# sixuanyi.net
KiCad netlist of a schematic drawn in Altium Designer
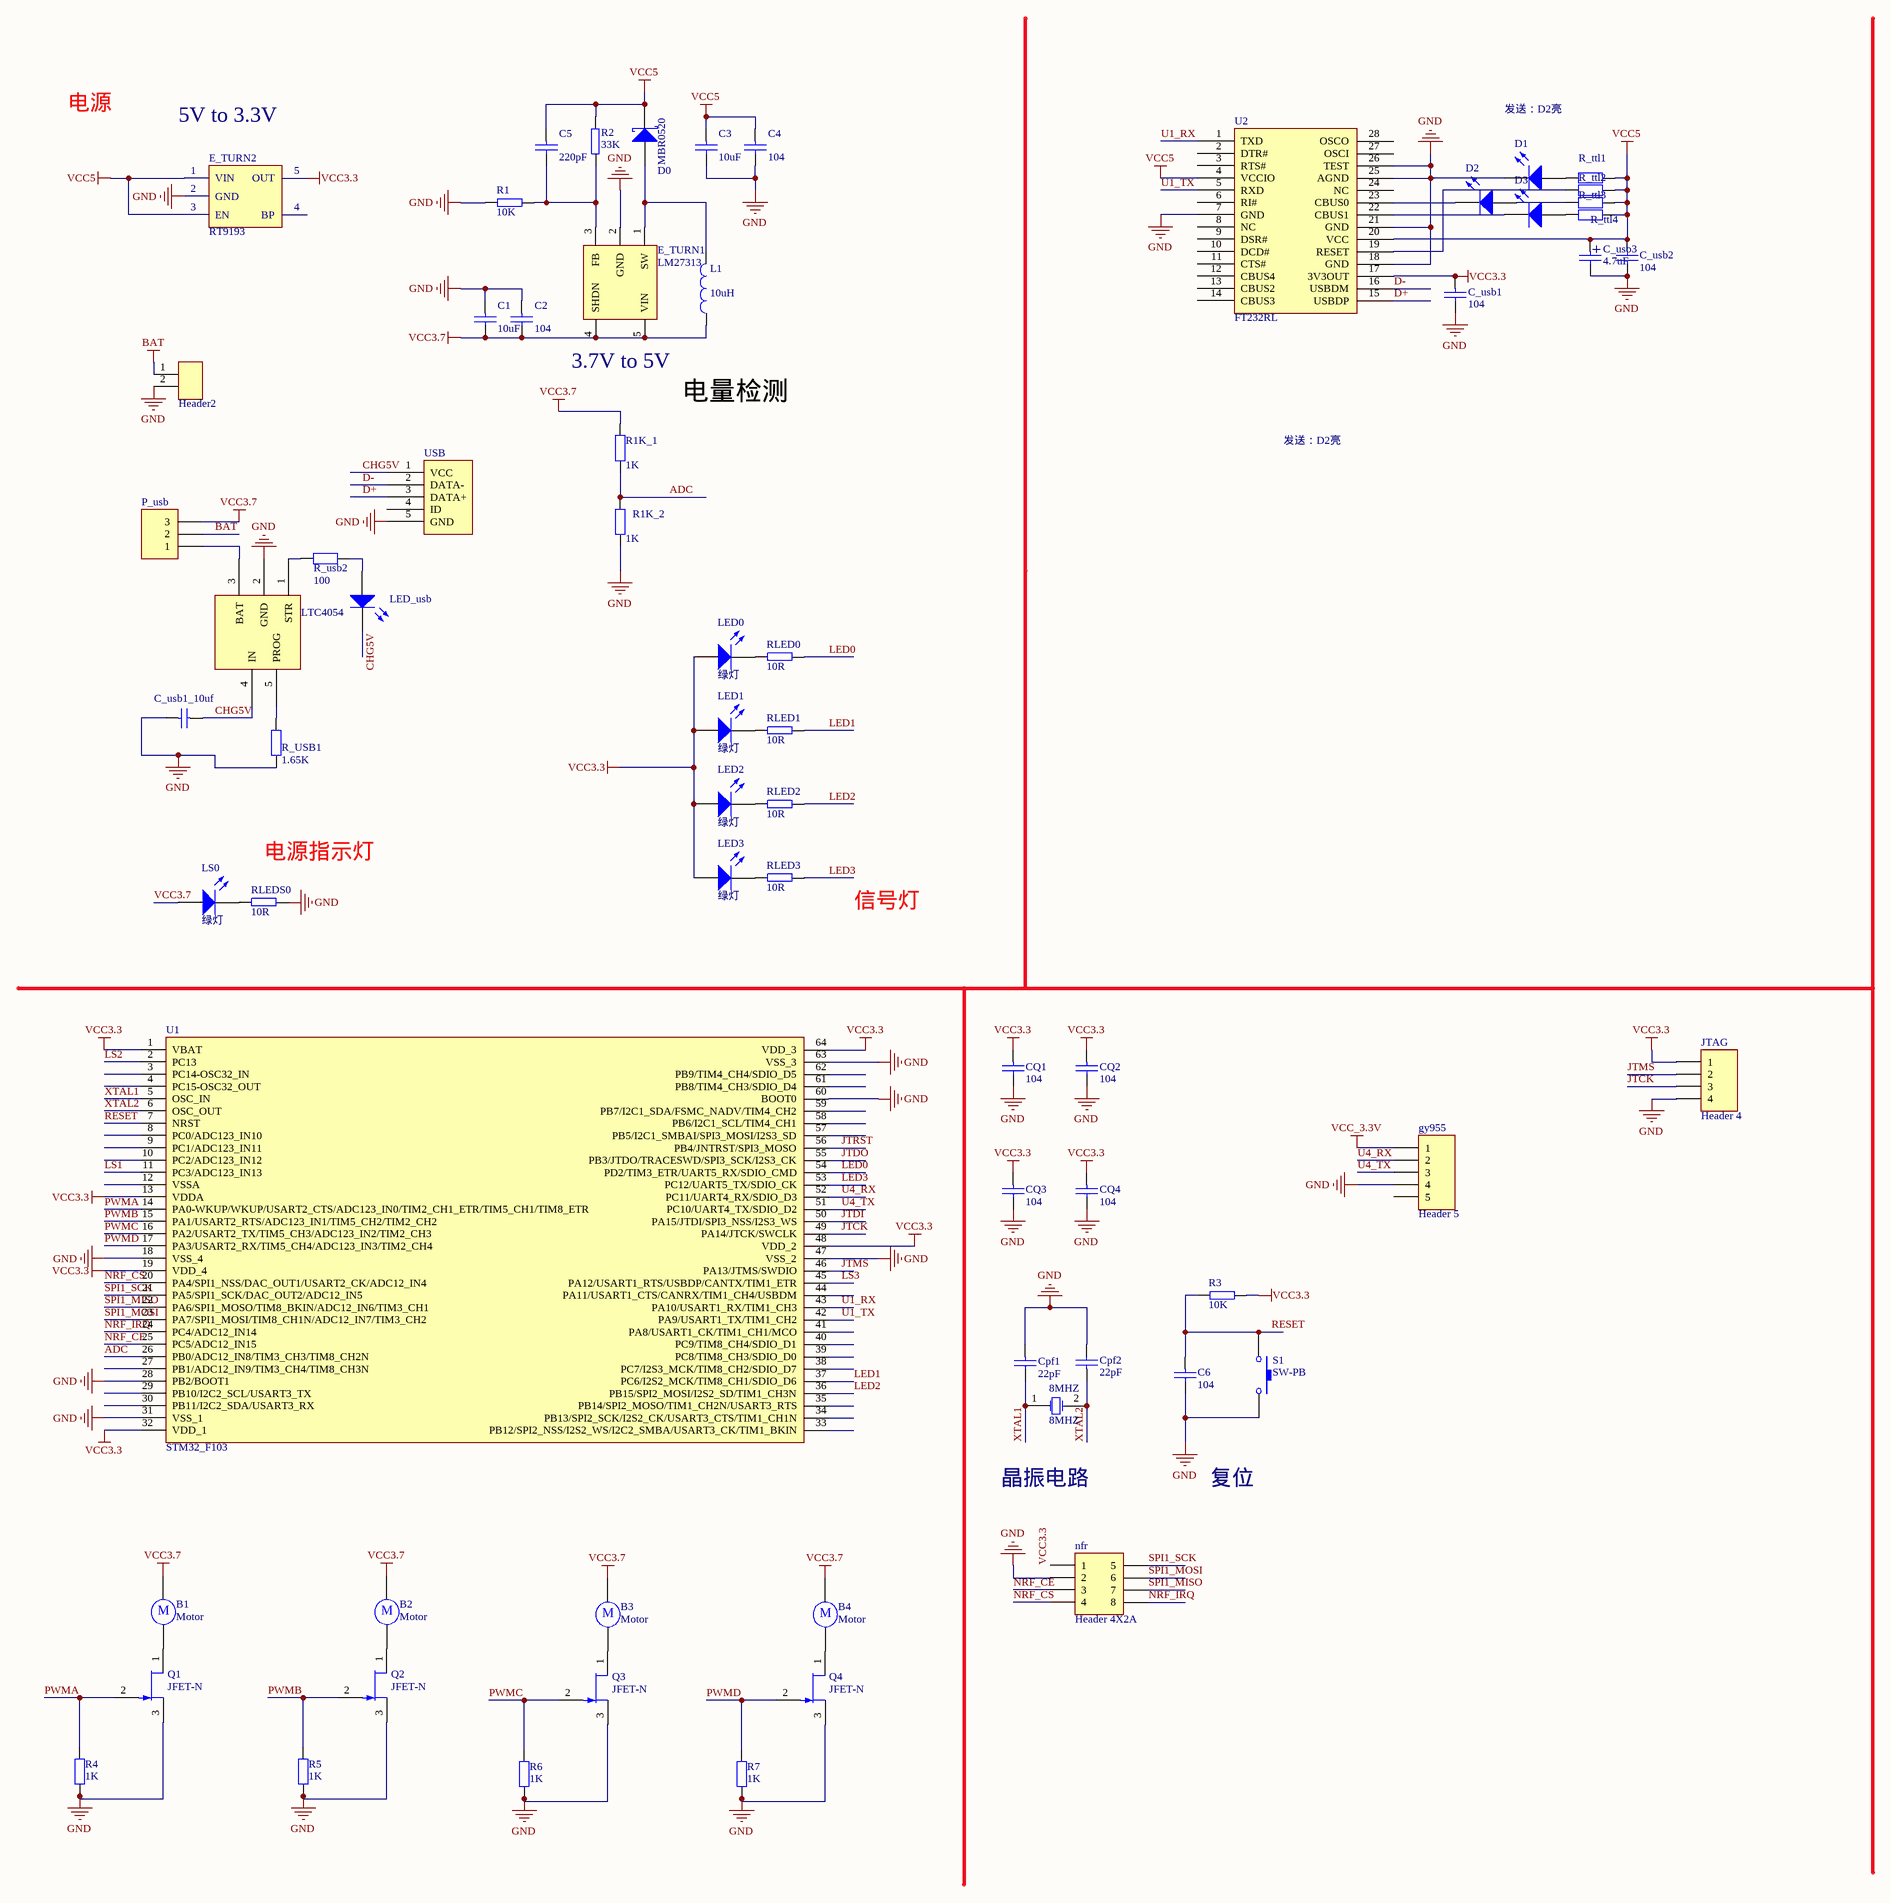
[diagram p0: sixuanyi.SchDoc]

(export (version "E")
  (design (tool "Eeschema 10.0.6"))
  (components
    (comp (ref "8MHZ")
      (value "8MHZ")
      (footprint "XTAL_D")
      (description "Crystal Oscillator")
      (fields (field (name "PUBLISHER") "Altium Limited"))
      (libsource (lib "TiCao") (part "XTAL"))
    )
    (comp (ref "B1")
      (value "Motor")
      (footprint "RB5-10.5")
      (description "Motor, General Kind")
      (fields (field (name "PUBLISHER") "Altium Limited"))
      (libsource (lib "Miscellaneous Devices") (part "Motor"))
    )
    (comp (ref "B2")
      (value "Motor")
      (footprint "RB5-10.5")
      (description "Motor, General Kind")
      (fields (field (name "PUBLISHER") "Altium Limited"))
      (libsource (lib "Miscellaneous Devices") (part "Motor"))
    )
    (comp (ref "B3")
      (value "Motor")
      (footprint "RB5-10.5")
      (description "Motor, General Kind")
      (fields (field (name "PUBLISHER") "Altium Limited"))
      (libsource (lib "Miscellaneous Devices") (part "Motor"))
    )
    (comp (ref "B4")
      (value "Motor")
      (footprint "RB5-10.5")
      (description "Motor, General Kind")
      (fields (field (name "PUBLISHER") "Altium Limited"))
      (libsource (lib "Miscellaneous Devices") (part "Motor"))
    )
    (comp (ref "C1") (value "10uF") (footprint "0603p") (libsource (lib "Sizhou") (part "CAP_WYN")))
    (comp (ref "C2") (value "104") (footprint "0603p") (libsource (lib "Sizhou") (part "CAP_WYN")))
    (comp (ref "C3") (value "10uF") (footprint "0603_WYN") (libsource (lib "Sizhou") (part "CAP_WYN")))
    (comp (ref "C4") (value "104") (footprint "0603_WYN") (libsource (lib "Sizhou") (part "CAP_WYN")))
    (comp (ref "C5") (value "220pF") (footprint "0603_WYN") (libsource (lib "Sizhou") (part "CAP_WYN")))
    (comp (ref "C6") (value "104") (footprint "0603_WYN") (libsource (lib "main") (part "CAP_WYN")))
    (comp (ref "Cpf1") (value "22pF") (footprint "0603_WYN") (libsource (lib "main") (part "CAP_WYN")))
    (comp (ref "Cpf2") (value "22pF") (footprint "0603_WYN") (libsource (lib "main") (part "CAP_WYN")))
    (comp (ref "CQ1") (value "104") (footprint "0603_WYN") (libsource (lib "main") (part "CAP_WYN")))
    (comp (ref "CQ2") (value "104") (footprint "0603_WYN") (libsource (lib "main") (part "CAP_WYN")))
    (comp (ref "CQ3") (value "104") (footprint "0603_WYN") (libsource (lib "main") (part "CAP_WYN")))
    (comp (ref "CQ4") (value "104") (footprint "0603_WYN") (libsource (lib "main") (part "CAP_WYN")))
    (comp (ref "C_usb1") (value "104") (footprint "0603P") (libsource (lib "main") (part "CAP_WYN")))
    (comp (ref "C_usb1_10uf")
      (value "C_usb1_10uf")
      (footprint "0603p")
      (description "Capacitor")
      (fields (field (name "PUBLISHER") "Altium Limited"))
      (libsource (lib "Miscellaneous Devices") (part "Cap"))
    )
    (comp (ref "C_usb2") (value "104") (footprint "0603P") (libsource (lib "main") (part "CAP_WYN")))
    (comp (ref "C_usb3")
      (value "4.7uF")
      (footprint "1206")
      (libsource (lib "PCB_PROJECT1") (part "CAP_POL_WYN"))
    )
    (comp (ref "D0")
      (value "MBR0520")
      (footprint "SMB")
      (description "Schottky Diode")
      (fields (field (name "PUBLISHER") "Altium Limited"))
      (libsource (lib "Miscellaneous Devices") (part "D Schottky"))
    )
    (comp (ref "D1")
      (value "LED2")
      (footprint "SMDLED")
      (description "Typical RED, GREEN, YELLOW, AMBER GaAs LED")
      (fields (field (name "PUBLISHER") "Altium Limited"))
      (libsource (lib "Miscellaneous Devices") (part "LED2"))
    )
    (comp (ref "D2")
      (value "LED2")
      (footprint "SMDLED")
      (description "Typical RED, GREEN, YELLOW, AMBER GaAs LED")
      (fields (field (name "PUBLISHER") "Altium Limited"))
      (libsource (lib "Miscellaneous Devices") (part "LED2"))
    )
    (comp (ref "D3")
      (value "LED2")
      (footprint "SMDLED")
      (description "Typical RED, GREEN, YELLOW, AMBER GaAs LED")
      (fields (field (name "PUBLISHER") "Altium Limited"))
      (libsource (lib "Miscellaneous Devices") (part "LED2"))
    )
    (comp (ref "E_TURN1") (value "LM27313") (footprint "SOT23-6") (libsource (lib "Sizhou") (part "LM27313")))
    (comp (ref "E_TURN2") (value "RT9193") (footprint "SOT23-6") (libsource (lib "Sizhou") (part "RT9193")))
    (comp (ref "gy955")
      (value "Header 5")
      (footprint "HDR1X5")
      (description "Header, 5-Pin")
      (fields (field (name "PUBLISHER") "Altium Limited"))
      (libsource (lib "Miscellaneous Connectors") (part "Header 5"))
    )
    (comp (ref "JTAG")
      (value "Header 4")
      (footprint "HDR1X4")
      (description "Header, 4-Pin")
      (fields (field (name "PUBLISHER") "Altium Limited"))
      (libsource (lib "Miscellaneous Connectors") (part "Header 4"))
    )
    (comp (ref "L1")
      (value "10uH")
      (footprint "0805_WYN")
      (description "Inductor")
      (fields (field (name "PUBLISHER") "Altium Limited"))
      (libsource (lib "Miscellaneous Devices") (part "Inductor"))
    )
    (comp (ref "LED0")
      (value "绿灯")
      (footprint "0603_WYN")
      (description "Typical RED, GREEN, YELLOW, AMBER GaAs LED")
      (fields (field (name "PUBLISHER") "Altium Limited"))
      (libsource (lib "main") (part "LED_WYN"))
    )
    (comp (ref "LED1")
      (value "绿灯")
      (footprint "0603_WYN")
      (description "Typical RED, GREEN, YELLOW, AMBER GaAs LED")
      (fields (field (name "PUBLISHER") "Altium Limited"))
      (libsource (lib "main") (part "LED_WYN"))
    )
    (comp (ref "LED2")
      (value "绿灯")
      (footprint "0603_WYN")
      (description "Typical RED, GREEN, YELLOW, AMBER GaAs LED")
      (fields (field (name "PUBLISHER") "Altium Limited"))
      (libsource (lib "main") (part "LED_WYN"))
    )
    (comp (ref "LED3")
      (value "绿灯")
      (footprint "0603_WYN")
      (description "Typical RED, GREEN, YELLOW, AMBER GaAs LED")
      (fields (field (name "PUBLISHER") "Altium Limited"))
      (libsource (lib "main") (part "LED_WYN"))
    )
    (comp (ref "LED_usb")
      (value "黄灯")
      (footprint "极性0805_WYN")
      (description "Typical RED GaAs LED")
      (fields (field (name "PUBLISHER") "Altium Limited"))
      (libsource (lib "救援1") (part "LED1"))
    )
    (comp (ref "LS0")
      (value "绿灯")
      (footprint "0603_WYN")
      (description "Typical RED, GREEN, YELLOW, AMBER GaAs LED")
      (fields (field (name "PUBLISHER") "Altium Limited"))
      (libsource (lib "main") (part "LED_WYN"))
    )
    (comp (ref "LTC4054") (value "LTC4054") (footprint "SOT23-6") (libsource (lib "救援2") (part "LTC4054")))
    (comp (ref "nfr")
      (value "Header 4X2A")
      (footprint "24L01-L")
      (description "Header, 4-Pin, Dual row")
      (fields (field (name "PUBLISHER") "Altium Limited"))
      (libsource (lib "Miscellaneous Connectors") (part "Header 4X2A"))
    )
    (comp (ref "power") (value "Header2") (footprint "HDR1X2") (libsource (lib "救援2") (part "Header2")))
    (comp (ref "P_usb")
      (value "P_usb")
      (footprint "HDR1X3")
      (description "Header, 3-Pin")
      (fields (field (name "PUBLISHER") "Altium Limited"))
      (libsource (lib "Miscellaneous Connectors") (part "Header 3"))
    )
    (comp (ref "Q1")
      (value "JFET-N")
      (footprint "SI2302")
      (description "N-Channel JFET")
      (fields (field (name "PUBLISHER") "Altium Limited"))
      (libsource (lib "Miscellaneous Devices") (part "JFET-N"))
    )
    (comp (ref "Q2")
      (value "JFET-N")
      (footprint "SI2302")
      (description "N-Channel JFET")
      (fields (field (name "PUBLISHER") "Altium Limited"))
      (libsource (lib "Miscellaneous Devices") (part "JFET-N"))
    )
    (comp (ref "Q3")
      (value "JFET-N")
      (footprint "SI2302")
      (description "N-Channel JFET")
      (fields (field (name "PUBLISHER") "Altium Limited"))
      (libsource (lib "Miscellaneous Devices") (part "JFET-N"))
    )
    (comp (ref "Q4")
      (value "JFET-N")
      (footprint "SI2302")
      (description "N-Channel JFET")
      (fields (field (name "PUBLISHER") "Altium Limited"))
      (libsource (lib "Miscellaneous Devices") (part "JFET-N"))
    )
    (comp (ref "R1") (value "10K") (footprint "0603_WYN") (libsource (lib "main") (part "RES_WYN")))
    (comp (ref "R1K_1")
      (value "1K")
      (footprint "AXIAL-0.4")
      (description "Resistor")
      (fields (field (name "Comment") "Res2") (field (name "PUBLISHER") "Altium Limited"))
      (libsource (lib "Miscellaneous Devices") (part "Res2"))
    )
    (comp (ref "R1K_2")
      (value "1K")
      (footprint "AXIAL-0.4")
      (description "Resistor")
      (fields (field (name "Comment") "Res2") (field (name "PUBLISHER") "Altium Limited"))
      (libsource (lib "Miscellaneous Devices") (part "Res2"))
    )
    (comp (ref "R2") (value "33K") (footprint "0603_WYN") (libsource (lib "main") (part "RES_WYN")))
    (comp (ref "R3") (value "10K") (footprint "0603_WYN") (libsource (lib "main") (part "RES_WYN")))
    (comp (ref "R4")
      (value "1K")
      (footprint "AXIAL-0.4")
      (description "Resistor")
      (fields (field (name "Comment") "Res2") (field (name "PUBLISHER") "Altium Limited"))
      (libsource (lib "Miscellaneous Devices") (part "Res2"))
    )
    (comp (ref "R5")
      (value "1K")
      (footprint "AXIAL-0.4")
      (description "Resistor")
      (fields (field (name "Comment") "Res2") (field (name "PUBLISHER") "Altium Limited"))
      (libsource (lib "Miscellaneous Devices") (part "Res2"))
    )
    (comp (ref "R6")
      (value "1K")
      (footprint "AXIAL-0.4")
      (description "Resistor")
      (fields (field (name "Comment") "Res2") (field (name "PUBLISHER") "Altium Limited"))
      (libsource (lib "Miscellaneous Devices") (part "Res2"))
    )
    (comp (ref "R7")
      (value "1K")
      (footprint "AXIAL-0.4")
      (description "Resistor")
      (fields (field (name "Comment") "Res2") (field (name "PUBLISHER") "Altium Limited"))
      (libsource (lib "Miscellaneous Devices") (part "Res2"))
    )
    (comp (ref "RLED0") (value "10R") (footprint "0603_WYN") (libsource (lib "main") (part "RES_WYN")))
    (comp (ref "RLED1") (value "10R") (footprint "0603_WYN") (libsource (lib "main") (part "RES_WYN")))
    (comp (ref "RLED2") (value "10R") (footprint "0603_WYN") (libsource (lib "main") (part "RES_WYN")))
    (comp (ref "RLED3") (value "10R") (footprint "0603_WYN") (libsource (lib "main") (part "RES_WYN")))
    (comp (ref "RLEDS0") (value "10R") (footprint "0603_WYN") (libsource (lib "main") (part "RES_WYN")))
    (comp (ref "R_ttl1")
      (value "1K")
      (footprint "0603p")
      (description "Resistor")
      (fields (field (name "PUBLISHER") "Altium Limited"))
      (libsource (lib "救援1") (part "Res2"))
    )
    (comp (ref "R_ttl2")
      (value "1K")
      (footprint "0603p")
      (description "Resistor")
      (fields (field (name "PUBLISHER") "Altium Limited"))
      (libsource (lib "救援1") (part "Res2"))
    )
    (comp (ref "R_ttl3")
      (value "1K")
      (footprint "0603p")
      (description "Resistor")
      (fields (field (name "PUBLISHER") "Altium Limited"))
      (libsource (lib "救援1") (part "Res2"))
    )
    (comp (ref "R_ttl4")
      (value "1K")
      (footprint "0603p")
      (description "Resistor")
      (fields (field (name "PUBLISHER") "Altium Limited"))
      (libsource (lib "救援1") (part "Res2"))
    )
    (comp (ref "R_USB1")
      (value "R_USB1")
      (footprint "0603p")
      (description "Resistor")
      (fields (field (name "ALTIUM_VALUE") "1.65K") (field (name "PUBLISHER") "Altium Limited"))
      (libsource (lib "Miscellaneous Devices") (part "Res2"))
    )
    (comp (ref "R_usb2")
      (value "R_usb2")
      (footprint "0603p")
      (description "Resistor")
      (fields (field (name "ALTIUM_VALUE") "100") (field (name "PUBLISHER") "Altium Limited"))
      (libsource (lib "") (part "Res2_1"))
    )
    (comp (ref "S1")
      (value "SW-PB")
      (footprint "CLICK")
      (description "Switch")
      (fields (field (name "PUBLISHER") "Altium Limited"))
      (libsource (lib "Miscellaneous Devices") (part "SW-PB"))
    )
    (comp (ref "U1") (value "STM32_F103") (footprint "LQFP64") (libsource (lib "tes1") (part "STM32_F103")))
    (comp (ref "U2") (value "FT232RL") (footprint "SSOP-28") (libsource (lib "my_library") (part "FT232RL")))
    (comp (ref "USB")
      (value "usb mini")
      (footprint "USB - duplicate1")
      (libsource (lib "救援2") (part "usb mini"))
    )
  )
  (nets
    (net (code "1") (name "/ADC") (class "Default")
      (node (ref "R1K_1") (pin "1") (pinfunction "1_1") (pintype "passive"))
      (node (ref "R1K_2") (pin "2") (pinfunction "2_2") (pintype "passive"))
      (node (ref "U1") (pin "26") (pinfunction "PB0/ADC12_IN8/TIM3_CH3/TIM8_CH2N_26") (pintype "passive"))
    )
    (net (code "2") (name "/CHG5V") (class "Default")
      (node (ref "C_usb1_10uf") (pin "1") (pinfunction "1_1") (pintype "passive"))
      (node (ref "LED_usb") (pin "2") (pinfunction "K_2") (pintype "passive"))
      (node (ref "LTC4054") (pin "4") (pinfunction "IN_4") (pintype "passive"))
      (node (ref "USB") (pin "1") (pinfunction "VCC_1") (pintype "passive"))
    )
    (net (code "3") (name "/D+") (class "Default")
      (node (ref "U2") (pin "15") (pinfunction "USBDP_15") (pintype "passive"))
      (node (ref "USB") (pin "3") (pinfunction "DATA+_3") (pintype "passive"))
    )
    (net (code "4") (name "/D-") (class "Default")
      (node (ref "U2") (pin "16") (pinfunction "USBDM_16") (pintype "passive"))
      (node (ref "USB") (pin "2") (pinfunction "DATA-_2") (pintype "passive"))
    )
    (net (code "5") (name "/JTCK") (class "Default")
      (node (ref "JTAG") (pin "3") (pinfunction "3_3") (pintype "passive"))
      (node (ref "U1") (pin "49") (pinfunction "PA14/JTCK/SWCLK_49") (pintype "passive"))
    )
    (net (code "6") (name "/JTDI") (class "Default")
      (node (ref "U1") (pin "50") (pinfunction "PA15/JTDI/SPI3_NSS/I2S3_WS_50") (pintype "passive"))
    )
    (net (code "7") (name "/JTDO") (class "Default")
      (node (ref "U1") (pin "55") (pinfunction "PB3/JTDO/TRACESWD/SPI3_SCK/I2S3_CK_55") (pintype "passive"))
    )
    (net (code "8") (name "/JTMS") (class "Default")
      (node (ref "JTAG") (pin "2") (pinfunction "2_2") (pintype "passive"))
      (node (ref "U1") (pin "46") (pinfunction "PA13/JTMS/SWDIO_46") (pintype "passive"))
    )
    (net (code "9") (name "/JTRST") (class "Default")
      (node (ref "U1") (pin "56") (pinfunction "PB4/JNTRST/SPI3_MOSO_56") (pintype "passive"))
    )
    (net (code "10") (name "/LED0") (class "Default")
      (node (ref "RLED0") (pin "1") (pinfunction "1_1") (pintype "passive"))
      (node (ref "U1") (pin "54") (pinfunction "PD2/TIM3_ETR/UART5_RX/SDIO_CMD_54") (pintype "passive"))
    )
    (net (code "11") (name "/LED1") (class "Default")
      (node (ref "RLED1") (pin "1") (pinfunction "1_1") (pintype "passive"))
      (node (ref "U1") (pin "37") (pinfunction "PC6/I2S2_MCK/TIM8_CH1/SDIO_D6_37") (pintype "passive"))
    )
    (net (code "12") (name "/LED2") (class "Default")
      (node (ref "RLED2") (pin "1") (pinfunction "1_1") (pintype "passive"))
      (node (ref "U1") (pin "36") (pinfunction "PB15/SPI2_MOSI/I2S2_SD/TIM1_CH3N_36") (pintype "passive"))
    )
    (net (code "13") (name "/LED3") (class "Default")
      (node (ref "RLED3") (pin "1") (pinfunction "1_1") (pintype "passive"))
      (node (ref "U1") (pin "53") (pinfunction "PC12/UART5_TX/SDIO_CK_53") (pintype "passive"))
    )
    (net (code "14") (name "/LS1") (class "Default")
      (node (ref "U1") (pin "11") (pinfunction "PC3/ADC123_IN13_11") (pintype "passive"))
    )
    (net (code "15") (name "/LS2") (class "Default")
      (node (ref "U1") (pin "2") (pinfunction "PC13_2") (pintype "passive"))
    )
    (net (code "16") (name "/LS3") (class "Default")
      (node (ref "U1") (pin "45") (pinfunction "PA12/USART1_RTS/USBDP/CANTX/TIM1_ETR_45") (pintype "passive"))
    )
    (net (code "17") (name "/NRF_CE") (class "Default")
      (node (ref "U1") (pin "25") (pinfunction "PC5/ADC12_IN15_25") (pintype "passive"))
      (node (ref "nfr") (pin "3") (pinfunction "3_3") (pintype "passive"))
    )
    (net (code "18") (name "/NRF_CS") (class "Default")
      (node (ref "U1") (pin "20") (pinfunction "PA4/SPI1_NSS/DAC_OUT1/USART2_CK/ADC12_IN4_20") (pintype "passive"))
      (node (ref "nfr") (pin "4") (pinfunction "4_4") (pintype "passive"))
    )
    (net (code "19") (name "/NRF_IRQ") (class "Default")
      (node (ref "U1") (pin "24") (pinfunction "PC4/ADC12_IN14_24") (pintype "passive"))
      (node (ref "nfr") (pin "8") (pinfunction "8_8") (pintype "passive"))
    )
    (net (code "20") (name "/PWMA") (class "Default")
      (node (ref "Q1") (pin "2") (pinfunction "G_2") (pintype "passive"))
      (node (ref "R4") (pin "2") (pinfunction "2_2") (pintype "passive"))
      (node (ref "U1") (pin "14") (pinfunction "PA0-WKUP/WKUP/USART2_CTS/ADC123_IN0/TIM2_CH1_ETR/TIM5_CH1/TIM8_ETR_14") (pintype "passive"))
    )
    (net (code "21") (name "/PWMB") (class "Default")
      (node (ref "Q2") (pin "2") (pinfunction "G_2") (pintype "passive"))
      (node (ref "R5") (pin "2") (pinfunction "2_2") (pintype "passive"))
      (node (ref "U1") (pin "15") (pinfunction "PA1/USART2_RTS/ADC123_IN1/TIM5_CH2/TIM2_CH2_15") (pintype "passive"))
    )
    (net (code "22") (name "/PWMC") (class "Default")
      (node (ref "Q3") (pin "2") (pinfunction "G_2") (pintype "passive"))
      (node (ref "R6") (pin "2") (pinfunction "2_2") (pintype "passive"))
      (node (ref "U1") (pin "16") (pinfunction "PA2/USART2_TX/TIM5_CH3/ADC123_IN2/TIM2_CH3_16") (pintype "passive"))
    )
    (net (code "23") (name "/PWMD") (class "Default")
      (node (ref "Q4") (pin "2") (pinfunction "G_2") (pintype "passive"))
      (node (ref "R7") (pin "2") (pinfunction "2_2") (pintype "passive"))
      (node (ref "U1") (pin "17") (pinfunction "PA3/USART2_RX/TIM5_CH4/ADC123_IN3/TIM2_CH4_17") (pintype "passive"))
    )
    (net (code "24") (name "/RESET") (class "Default")
      (node (ref "C6") (pin "1") (pintype "passive"))
      (node (ref "R3") (pin "1") (pinfunction "1_1") (pintype "passive"))
      (node (ref "S1") (pin "1") (pinfunction "1_1") (pintype "passive"))
      (node (ref "U1") (pin "7") (pinfunction "NRST_7") (pintype "passive"))
    )
    (net (code "25") (name "/SPI1_MISO") (class "Default")
      (node (ref "U1") (pin "22") (pinfunction "PA6/SPI1_MOSO/TIM8_BKIN/ADC12_IN6/TIM3_CH1_22") (pintype "passive"))
      (node (ref "nfr") (pin "7") (pinfunction "7_7") (pintype "passive"))
    )
    (net (code "26") (name "/SPI1_MOSI") (class "Default")
      (node (ref "U1") (pin "23") (pinfunction "PA7/SPI1_MOSI/TIM8_CH1N/ADC12_IN7/TIM3_CH2_23") (pintype "passive"))
      (node (ref "nfr") (pin "6") (pinfunction "6_6") (pintype "passive"))
    )
    (net (code "27") (name "/SPI1_SCK") (class "Default")
      (node (ref "U1") (pin "21") (pinfunction "PA5/SPI1_SCK/DAC_OUT2/ADC12_IN5_21") (pintype "passive"))
      (node (ref "nfr") (pin "5") (pinfunction "5_5") (pintype "passive"))
    )
    (net (code "28") (name "/U1_RX") (class "Default")
      (node (ref "U1") (pin "43") (pinfunction "PA10/USART1_RX/TIM1_CH3_43") (pintype "passive"))
      (node (ref "U2") (pin "1") (pinfunction "TXD_1") (pintype "passive"))
    )
    (net (code "29") (name "/U1_TX") (class "Default")
      (node (ref "U1") (pin "42") (pinfunction "PA9/USART1_TX/TIM1_CH2_42") (pintype "passive"))
      (node (ref "U2") (pin "5") (pinfunction "RXD_5") (pintype "passive"))
    )
    (net (code "30") (name "/U4_RX") (class "Default")
      (node (ref "U1") (pin "52") (pinfunction "PC11/UART4_RX/SDIO_D3_52") (pintype "passive"))
      (node (ref "gy955") (pin "2") (pinfunction "2_2") (pintype "passive"))
    )
    (net (code "31") (name "/U4_TX") (class "Default")
      (node (ref "U1") (pin "51") (pinfunction "PC10/UART4_TX/SDIO_D2_51") (pintype "passive"))
      (node (ref "gy955") (pin "3") (pinfunction "3_3") (pintype "passive"))
    )
    (net (code "32") (name "/XTAL1") (class "Default")
      (node (ref "8MHZ") (pin "1") (pinfunction "OSC1_1") (pintype "passive"))
      (node (ref "Cpf1") (pin "2") (pintype "passive"))
      (node (ref "U1") (pin "5") (pinfunction "OSC_IN_5") (pintype "passive"))
    )
    (net (code "33") (name "/XTAL2") (class "Default")
      (node (ref "8MHZ") (pin "2") (pinfunction "OSC2_2") (pintype "passive"))
      (node (ref "Cpf2") (pin "1") (pintype "passive"))
      (node (ref "U1") (pin "6") (pinfunction "OSC_OUT_6") (pintype "passive"))
    )
    (net (code "34") (name "BAT") (class "Default")
      (node (ref "P_usb") (pin "2") (pinfunction "2_2") (pintype "passive"))
      (node (ref "power") (pin "1") (pintype "passive"))
    )
    (net (code "35") (name "GND") (class "Default")
      (node (ref "C1") (pin "1") (pintype "passive"))
      (node (ref "C2") (pin "1") (pintype "passive"))
      (node (ref "C3") (pin "2") (pintype "passive"))
      (node (ref "C4") (pin "2") (pintype "passive"))
      (node (ref "C6") (pin "2") (pintype "passive"))
      (node (ref "CQ1") (pin "2") (pintype "passive"))
      (node (ref "CQ2") (pin "2") (pintype "passive"))
      (node (ref "CQ3") (pin "2") (pintype "passive"))
      (node (ref "CQ4") (pin "2") (pintype "passive"))
      (node (ref "C_usb1") (pin "2") (pintype "passive"))
      (node (ref "C_usb1_10uf") (pin "2") (pinfunction "2_2") (pintype "passive"))
      (node (ref "C_usb2") (pin "2") (pintype "passive"))
      (node (ref "C_usb3") (pin "2") (pintype "passive"))
      (node (ref "Cpf1") (pin "1") (pintype "passive"))
      (node (ref "Cpf2") (pin "2") (pintype "passive"))
      (node (ref "D1") (pin "2") (pinfunction "K_2") (pintype "passive"))
      (node (ref "E_TURN1") (pin "2") (pinfunction "GND_2") (pintype "passive"))
      (node (ref "E_TURN2") (pin "2") (pinfunction "GND_2") (pintype "passive"))
      (node (ref "JTAG") (pin "4") (pinfunction "4_4") (pintype "passive"))
      (node (ref "LTC4054") (pin "2") (pinfunction "GND_2") (pintype "passive"))
      (node (ref "Q1") (pin "3") (pinfunction "S_3") (pintype "passive"))
      (node (ref "Q2") (pin "3") (pinfunction "S_3") (pintype "passive"))
      (node (ref "Q3") (pin "3") (pinfunction "S_3") (pintype "passive"))
      (node (ref "Q4") (pin "3") (pinfunction "S_3") (pintype "passive"))
      (node (ref "R1") (pin "1") (pinfunction "1_1") (pintype "passive"))
      (node (ref "R1K_2") (pin "1") (pinfunction "1_1") (pintype "passive"))
      (node (ref "R4") (pin "1") (pinfunction "1_1") (pintype "passive"))
      (node (ref "R5") (pin "1") (pinfunction "1_1") (pintype "passive"))
      (node (ref "R6") (pin "1") (pinfunction "1_1") (pintype "passive"))
      (node (ref "R7") (pin "1") (pinfunction "1_1") (pintype "passive"))
      (node (ref "RLEDS0") (pin "1") (pinfunction "1_1") (pintype "passive"))
      (node (ref "R_USB1") (pin "1") (pinfunction "1_1") (pintype "passive"))
      (node (ref "S1") (pin "2") (pinfunction "2_2") (pintype "passive"))
      (node (ref "U1") (pin "18") (pinfunction "VSS_4_18") (pintype "passive"))
      (node (ref "U1") (pin "28") (pinfunction "PB2/BOOT1_28") (pintype "passive"))
      (node (ref "U1") (pin "31") (pinfunction "VSS_1_31") (pintype "passive"))
      (node (ref "U1") (pin "47") (pinfunction "VSS_2_47") (pintype "passive"))
      (node (ref "U1") (pin "60") (pinfunction "BOOT0_60") (pintype "passive"))
      (node (ref "U1") (pin "63") (pinfunction "VSS_3_63") (pintype "passive"))
      (node (ref "U2") (pin "18") (pinfunction "GND_18") (pintype "passive"))
      (node (ref "U2") (pin "21") (pinfunction "GND_21") (pintype "passive"))
      (node (ref "U2") (pin "25") (pinfunction "AGND_25") (pintype "passive"))
      (node (ref "U2") (pin "26") (pinfunction "TEST_26") (pintype "passive"))
      (node (ref "U2") (pin "7") (pinfunction "GND_7") (pintype "passive"))
      (node (ref "USB") (pin "5") (pinfunction "GND_5") (pintype "passive"))
      (node (ref "gy955") (pin "4") (pinfunction "4_4") (pintype "passive"))
      (node (ref "nfr") (pin "2") (pinfunction "2_2") (pintype "passive"))
      (node (ref "power") (pin "2") (pintype "passive"))
    )
    (net (code "36") (name "Net-(D0-A)") (class "Default")
      (node (ref "D0") (pin "1") (pinfunction "A_1") (pintype "passive"))
      (node (ref "E_TURN1") (pin "1") (pinfunction "SW_1") (pintype "passive"))
      (node (ref "L1") (pin "2") (pinfunction "2_2") (pintype "passive"))
    )
    (net (code "37") (name "Net-(D1-A)") (class "Default")
      (node (ref "D1") (pin "1") (pinfunction "A_1") (pintype "passive"))
      (node (ref "R_ttl1") (pin "1") (pinfunction "1_1") (pintype "passive"))
    )
    (net (code "38") (name "Net-(D2-A)") (class "Default")
      (node (ref "D2") (pin "1") (pinfunction "A_1") (pintype "passive"))
      (node (ref "R_ttl3") (pin "1") (pinfunction "1_1") (pintype "passive"))
    )
    (net (code "39") (name "Net-(D2-K)") (class "Default")
      (node (ref "D2") (pin "2") (pinfunction "K_2") (pintype "passive"))
      (node (ref "U2") (pin "23") (pinfunction "CBUS0_23") (pintype "passive"))
    )
    (net (code "40") (name "Net-(D3-A)") (class "Default")
      (node (ref "D3") (pin "1") (pinfunction "A_1") (pintype "passive"))
      (node (ref "R_ttl4") (pin "1") (pinfunction "1_1") (pintype "passive"))
    )
    (net (code "41") (name "Net-(D3-K)") (class "Default")
      (node (ref "D3") (pin "2") (pinfunction "K_2") (pintype "passive"))
      (node (ref "U2") (pin "22") (pinfunction "CBUS1_22") (pintype "passive"))
    )
    (net (code "42") (name "Net-(E_TURN1-FB)") (class "Default")
      (node (ref "C5") (pin "2") (pintype "passive"))
      (node (ref "E_TURN1") (pin "3") (pinfunction "FB_3") (pintype "passive"))
      (node (ref "R1") (pin "2") (pinfunction "2_2") (pintype "passive"))
      (node (ref "R2") (pin "1") (pinfunction "1_1") (pintype "passive"))
    )
    (net (code "43") (name "Net-(LED0-K)") (class "Default")
      (node (ref "LED0") (pin "2") (pinfunction "K_2") (pintype "passive"))
      (node (ref "RLED0") (pin "2") (pinfunction "2_2") (pintype "passive"))
    )
    (net (code "44") (name "Net-(LED1-K)") (class "Default")
      (node (ref "LED1") (pin "2") (pinfunction "K_2") (pintype "passive"))
      (node (ref "RLED1") (pin "2") (pinfunction "2_2") (pintype "passive"))
    )
    (net (code "45") (name "Net-(LED2-K)") (class "Default")
      (node (ref "LED2") (pin "2") (pinfunction "K_2") (pintype "passive"))
      (node (ref "RLED2") (pin "2") (pinfunction "2_2") (pintype "passive"))
    )
    (net (code "46") (name "Net-(LED3-K)") (class "Default")
      (node (ref "LED3") (pin "2") (pinfunction "K_2") (pintype "passive"))
      (node (ref "RLED3") (pin "2") (pinfunction "2_2") (pintype "passive"))
    )
    (net (code "47") (name "Net-(LED_usb-A)") (class "Default")
      (node (ref "LED_usb") (pin "1") (pinfunction "A_1") (pintype "passive"))
      (node (ref "R_usb2") (pin "2") (pinfunction "2_2") (pintype "passive"))
    )
    (net (code "48") (name "Net-(LS0-K)") (class "Default")
      (node (ref "LS0") (pin "2") (pinfunction "K_2") (pintype "passive"))
      (node (ref "RLEDS0") (pin "2") (pinfunction "2_2") (pintype "passive"))
    )
    (net (code "49") (name "Net-(LTC4054-BAT)") (class "Default")
      (node (ref "LTC4054") (pin "3") (pinfunction "BAT_3") (pintype "passive"))
      (node (ref "P_usb") (pin "1") (pinfunction "1_1") (pintype "passive"))
    )
    (net (code "50") (name "Net-(LTC4054-PROG)") (class "Default")
      (node (ref "LTC4054") (pin "5") (pinfunction "PROG_5") (pintype "passive"))
      (node (ref "R_USB1") (pin "2") (pinfunction "2_2") (pintype "passive"))
    )
    (net (code "51") (name "Net-(LTC4054-STR)") (class "Default")
      (node (ref "LTC4054") (pin "1") (pinfunction "STR_1") (pintype "passive"))
      (node (ref "R_usb2") (pin "1") (pinfunction "1_1") (pintype "passive"))
    )
    (net (code "52") (name "Net-(Q1-D)") (class "Default")
      (node (ref "B1") (pin "2") (pinfunction "2_2") (pintype "passive"))
      (node (ref "Q1") (pin "1") (pinfunction "D_1") (pintype "passive"))
    )
    (net (code "53") (name "Net-(Q2-D)") (class "Default")
      (node (ref "B2") (pin "2") (pinfunction "2_2") (pintype "passive"))
      (node (ref "Q2") (pin "1") (pinfunction "D_1") (pintype "passive"))
    )
    (net (code "54") (name "Net-(Q3-D)") (class "Default")
      (node (ref "B3") (pin "2") (pinfunction "2_2") (pintype "passive"))
      (node (ref "Q3") (pin "1") (pinfunction "D_1") (pintype "passive"))
    )
    (net (code "55") (name "Net-(Q4-D)") (class "Default")
      (node (ref "B4") (pin "2") (pinfunction "2_2") (pintype "passive"))
      (node (ref "Q4") (pin "1") (pinfunction "D_1") (pintype "passive"))
    )
    (net (code "56") (name "Net-(U2-RESET)") (class "Default")
      (node (ref "R_ttl2") (pin "1") (pinfunction "1_1") (pintype "passive"))
      (node (ref "U2") (pin "19") (pinfunction "RESET_19") (pintype "passive"))
    )
    (net (code "57") (name "VCC3.3") (class "Default")
      (node (ref "CQ1") (pin "1") (pintype "passive"))
      (node (ref "CQ2") (pin "1") (pintype "passive"))
      (node (ref "CQ3") (pin "1") (pintype "passive"))
      (node (ref "CQ4") (pin "1") (pintype "passive"))
      (node (ref "C_usb1") (pin "1") (pintype "passive"))
      (node (ref "E_TURN2") (pin "5") (pinfunction "OUT_5") (pintype "passive"))
      (node (ref "JTAG") (pin "1") (pinfunction "1_1") (pintype "passive"))
      (node (ref "LED0") (pin "1") (pinfunction "A_1") (pintype "passive"))
      (node (ref "LED1") (pin "1") (pinfunction "A_1") (pintype "passive"))
      (node (ref "LED2") (pin "1") (pinfunction "A_1") (pintype "passive"))
      (node (ref "LED3") (pin "1") (pinfunction "A_1") (pintype "passive"))
      (node (ref "R3") (pin "2") (pinfunction "2_2") (pintype "passive"))
      (node (ref "U1") (pin "1") (pinfunction "VBAT_1") (pintype "passive"))
      (node (ref "U1") (pin "13") (pinfunction "VDDA_13") (pintype "passive"))
      (node (ref "U1") (pin "19") (pinfunction "VDD_4_19") (pintype "passive"))
      (node (ref "U1") (pin "32") (pinfunction "VDD_1_32") (pintype "passive"))
      (node (ref "U1") (pin "48") (pinfunction "VDD_2_48") (pintype "passive"))
      (node (ref "U1") (pin "64") (pinfunction "VDD_3_64") (pintype "passive"))
      (node (ref "U2") (pin "17") (pinfunction "3V3OUT_17") (pintype "passive"))
      (node (ref "nfr") (pin "1") (pinfunction "1_1") (pintype "passive"))
    )
    (net (code "58") (name "VCC3.7") (class "Default")
      (node (ref "B1") (pin "1") (pinfunction "1_1") (pintype "passive"))
      (node (ref "B2") (pin "1") (pinfunction "1_1") (pintype "passive"))
      (node (ref "B3") (pin "1") (pinfunction "1_1") (pintype "passive"))
      (node (ref "B4") (pin "1") (pinfunction "1_1") (pintype "passive"))
      (node (ref "C1") (pin "2") (pintype "passive"))
      (node (ref "C2") (pin "2") (pintype "passive"))
      (node (ref "E_TURN1") (pin "4") (pinfunction "SHDN_4") (pintype "passive"))
      (node (ref "E_TURN1") (pin "5") (pinfunction "VIN_5") (pintype "passive"))
      (node (ref "L1") (pin "1") (pinfunction "1_1") (pintype "passive"))
      (node (ref "LS0") (pin "1") (pinfunction "A_1") (pintype "passive"))
      (node (ref "P_usb") (pin "3") (pinfunction "3_3") (pintype "passive"))
      (node (ref "R1K_1") (pin "2") (pinfunction "2_2") (pintype "passive"))
    )
    (net (code "59") (name "VCC5") (class "Default")
      (node (ref "C3") (pin "1") (pintype "passive"))
      (node (ref "C4") (pin "1") (pintype "passive"))
      (node (ref "C5") (pin "1") (pintype "passive"))
      (node (ref "C_usb2") (pin "1") (pintype "passive"))
      (node (ref "C_usb3") (pin "1") (pintype "passive"))
      (node (ref "D0") (pin "2") (pinfunction "K_2") (pintype "passive"))
      (node (ref "E_TURN2") (pin "1") (pinfunction "VIN_1") (pintype "passive"))
      (node (ref "E_TURN2") (pin "3") (pinfunction "EN_3") (pintype "passive"))
      (node (ref "R2") (pin "2") (pinfunction "2_2") (pintype "passive"))
      (node (ref "R_ttl1") (pin "2") (pinfunction "2_2") (pintype "passive"))
      (node (ref "R_ttl2") (pin "2") (pinfunction "2_2") (pintype "passive"))
      (node (ref "R_ttl3") (pin "2") (pinfunction "2_2") (pintype "passive"))
      (node (ref "R_ttl4") (pin "2") (pinfunction "2_2") (pintype "passive"))
      (node (ref "U2") (pin "20") (pinfunction "VCC_20") (pintype "passive"))
      (node (ref "U2") (pin "4") (pinfunction "VCCIO_4") (pintype "passive"))
    )
    (net (code "60") (name "VCC_3.3V") (class "Default")
      (node (ref "gy955") (pin "1") (pinfunction "1_1") (pintype "passive"))
    )
    (net (code "61") (name "unconnected-(E_TURN2-BP-Pad4)") (class "Default")
      (node (ref "E_TURN2") (pin "4") (pinfunction "BP_4") (pintype "passive"))
    )
    (net (code "62") (name "unconnected-(U1-PA8{slash}USART1_CK{slash}TIM1_CH1{slash}MCO-Pad41)") (class "Default")
      (node (ref "U1") (pin "41") (pinfunction "PA8/USART1_CK/TIM1_CH1/MCO_41") (pintype "passive"))
    )
    (net (code "63") (name "unconnected-(U1-PA11{slash}USART1_CTS{slash}CANRX{slash}TIM1_CH4{slash}USBDM-Pad44)") (class "Default")
      (node (ref "U1") (pin "44") (pinfunction "PA11/USART1_CTS/CANRX/TIM1_CH4/USBDM_44") (pintype "passive"))
    )
    (net (code "64") (name "unconnected-(U1-PB1{slash}ADC12_IN9{slash}TIM3_CH4{slash}TIM8_CH3N-Pad27)") (class "Default")
      (node (ref "U1") (pin "27") (pinfunction "PB1/ADC12_IN9/TIM3_CH4/TIM8_CH3N_27") (pintype "passive"))
    )
    (net (code "65") (name "unconnected-(U1-PB5{slash}I2C1_SMBAI{slash}SPI3_MOSI{slash}I2S3_SD-Pad57)") (class "Default")
      (node (ref "U1") (pin "57") (pinfunction "PB5/I2C1_SMBAI/SPI3_MOSI/I2S3_SD_57") (pintype "passive"))
    )
    (net (code "66") (name "unconnected-(U1-PB6{slash}I2C1_SCL{slash}TIM4_CH1-Pad58)") (class "Default")
      (node (ref "U1") (pin "58") (pinfunction "PB6/I2C1_SCL/TIM4_CH1_58") (pintype "passive"))
    )
    (net (code "67") (name "unconnected-(U1-PB7{slash}I2C1_SDA{slash}FSMC_NADV{slash}TIM4_CH2-Pad59)") (class "Default")
      (node (ref "U1") (pin "59") (pinfunction "PB7/I2C1_SDA/FSMC_NADV/TIM4_CH2_59") (pintype "passive"))
    )
    (net (code "68") (name "unconnected-(U1-PB8{slash}TIM4_CH3{slash}SDIO_D4-Pad61)") (class "Default")
      (node (ref "U1") (pin "61") (pinfunction "PB8/TIM4_CH3/SDIO_D4_61") (pintype "passive"))
    )
    (net (code "69") (name "unconnected-(U1-PB9{slash}TIM4_CH4{slash}SDIO_D5-Pad62)") (class "Default")
      (node (ref "U1") (pin "62") (pinfunction "PB9/TIM4_CH4/SDIO_D5_62") (pintype "passive"))
    )
    (net (code "70") (name "unconnected-(U1-PB10{slash}I2C2_SCL{slash}USART3_TX-Pad29)") (class "Default")
      (node (ref "U1") (pin "29") (pinfunction "PB10/I2C2_SCL/USART3_TX_29") (pintype "passive"))
    )
    (net (code "71") (name "unconnected-(U1-PB11{slash}I2C2_SDA{slash}USART3_RX-Pad30)") (class "Default")
      (node (ref "U1") (pin "30") (pinfunction "PB11/I2C2_SDA/USART3_RX_30") (pintype "passive"))
    )
    (net (code "72") (name "unconnected-(U1-PB12{slash}SPI2_NSS{slash}I2S2_WS{slash}I2C2_SMBA{slash}USART3_CK{slash}TIM1_BKIN-Pad33)") (class "Default")
      (node (ref "U1") (pin "33") (pinfunction "PB12/SPI2_NSS/I2S2_WS/I2C2_SMBA/USART3_CK/TIM1_BKIN_33") (pintype "passive"))
    )
    (net (code "73") (name "unconnected-(U1-PB13{slash}SPI2_SCK{slash}I2S2_CK{slash}USART3_CTS{slash}TIM1_CH1N-Pad34)") (class "Default")
      (node (ref "U1") (pin "34") (pinfunction "PB13/SPI2_SCK/I2S2_CK/USART3_CTS/TIM1_CH1N_34") (pintype "passive"))
    )
    (net (code "74") (name "unconnected-(U1-PB14{slash}SPI2_MOSO{slash}TIM1_CH2N{slash}USART3_RTS-Pad35)") (class "Default")
      (node (ref "U1") (pin "35") (pinfunction "PB14/SPI2_MOSO/TIM1_CH2N/USART3_RTS_35") (pintype "passive"))
    )
    (net (code "75") (name "unconnected-(U1-PC0{slash}ADC123_IN10-Pad8)") (class "Default")
      (node (ref "U1") (pin "8") (pinfunction "PC0/ADC123_IN10_8") (pintype "passive"))
    )
    (net (code "76") (name "unconnected-(U1-PC1{slash}ADC123_IN11-Pad9)") (class "Default")
      (node (ref "U1") (pin "9") (pinfunction "PC1/ADC123_IN11_9") (pintype "passive"))
    )
    (net (code "77") (name "unconnected-(U1-PC2{slash}ADC123_IN12-Pad10)") (class "Default")
      (node (ref "U1") (pin "10") (pinfunction "PC2/ADC123_IN12_10") (pintype "passive"))
    )
    (net (code "78") (name "unconnected-(U1-PC7{slash}I2S3_MCK{slash}TIM8_CH2{slash}SDIO_D7-Pad38)") (class "Default")
      (node (ref "U1") (pin "38") (pinfunction "PC7/I2S3_MCK/TIM8_CH2/SDIO_D7_38") (pintype "passive"))
    )
    (net (code "79") (name "unconnected-(U1-PC8{slash}TIM8_CH3{slash}SDIO_D0-Pad39)") (class "Default")
      (node (ref "U1") (pin "39") (pinfunction "PC8/TIM8_CH3/SDIO_D0_39") (pintype "passive"))
    )
    (net (code "80") (name "unconnected-(U1-PC9{slash}TIM8_CH4{slash}SDIO_D1-Pad40)") (class "Default")
      (node (ref "U1") (pin "40") (pinfunction "PC9/TIM8_CH4/SDIO_D1_40") (pintype "passive"))
    )
    (net (code "81") (name "unconnected-(U1-PC14-OSC32_IN-Pad3)") (class "Default")
      (node (ref "U1") (pin "3") (pinfunction "PC14-OSC32_IN_3") (pintype "passive"))
    )
    (net (code "82") (name "unconnected-(U1-PC15-OSC32_OUT-Pad4)") (class "Default")
      (node (ref "U1") (pin "4") (pinfunction "PC15-OSC32_OUT_4") (pintype "passive"))
    )
    (net (code "83") (name "unconnected-(U1-VSSA-Pad12)") (class "Default")
      (node (ref "U1") (pin "12") (pinfunction "VSSA_12") (pintype "passive"))
    )
    (net (code "84") (name "unconnected-(U2-CBUS2-Pad13)") (class "Default")
      (node (ref "U2") (pin "13") (pinfunction "CBUS2_13") (pintype "passive"))
    )
    (net (code "85") (name "unconnected-(U2-CBUS3-Pad14)") (class "Default")
      (node (ref "U2") (pin "14") (pinfunction "CBUS3_14") (pintype "passive"))
    )
    (net (code "86") (name "unconnected-(U2-CBUS4-Pad12)") (class "Default")
      (node (ref "U2") (pin "12") (pinfunction "CBUS4_12") (pintype "passive"))
    )
    (net (code "87") (name "unconnected-(U2-CTS#-Pad11)") (class "Default")
      (node (ref "U2") (pin "11") (pinfunction "CTS#_11") (pintype "passive"))
    )
    (net (code "88") (name "unconnected-(U2-DCD#-Pad10)") (class "Default")
      (node (ref "U2") (pin "10") (pinfunction "DCD#_10") (pintype "passive"))
    )
    (net (code "89") (name "unconnected-(U2-DSR#-Pad9)") (class "Default")
      (node (ref "U2") (pin "9") (pinfunction "DSR#_9") (pintype "passive"))
    )
    (net (code "90") (name "unconnected-(U2-DTR#-Pad2)") (class "Default")
      (node (ref "U2") (pin "2") (pinfunction "DTR#_2") (pintype "passive"))
    )
    (net (code "91") (name "unconnected-(U2-NC-Pad8)") (class "Default")
      (node (ref "U2") (pin "8") (pinfunction "NC_8") (pintype "passive"))
    )
    (net (code "92") (name "unconnected-(U2-NC-Pad24)") (class "Default")
      (node (ref "U2") (pin "24") (pinfunction "NC_24") (pintype "passive"))
    )
    (net (code "93") (name "unconnected-(U2-OSCI-Pad27)") (class "Default")
      (node (ref "U2") (pin "27") (pinfunction "OSCI_27") (pintype "passive"))
    )
    (net (code "94") (name "unconnected-(U2-OSCO-Pad28)") (class "Default")
      (node (ref "U2") (pin "28") (pinfunction "OSCO_28") (pintype "passive"))
    )
    (net (code "95") (name "unconnected-(U2-RI#-Pad6)") (class "Default")
      (node (ref "U2") (pin "6") (pinfunction "RI#_6") (pintype "passive"))
    )
    (net (code "96") (name "unconnected-(U2-RTS#-Pad3)") (class "Default")
      (node (ref "U2") (pin "3") (pinfunction "RTS#_3") (pintype "passive"))
    )
    (net (code "97") (name "unconnected-(USB-ID-Pad4)") (class "Default")
      (node (ref "USB") (pin "4") (pinfunction "ID_4") (pintype "passive"))
    )
    (net (code "98") (name "unconnected-(gy955-Pad5)") (class "Default")
      (node (ref "gy955") (pin "5") (pinfunction "5_5") (pintype "passive"))
    )
  )
)
